# Power.net
KiCad netlist of a schematic drawn in Altium Designer
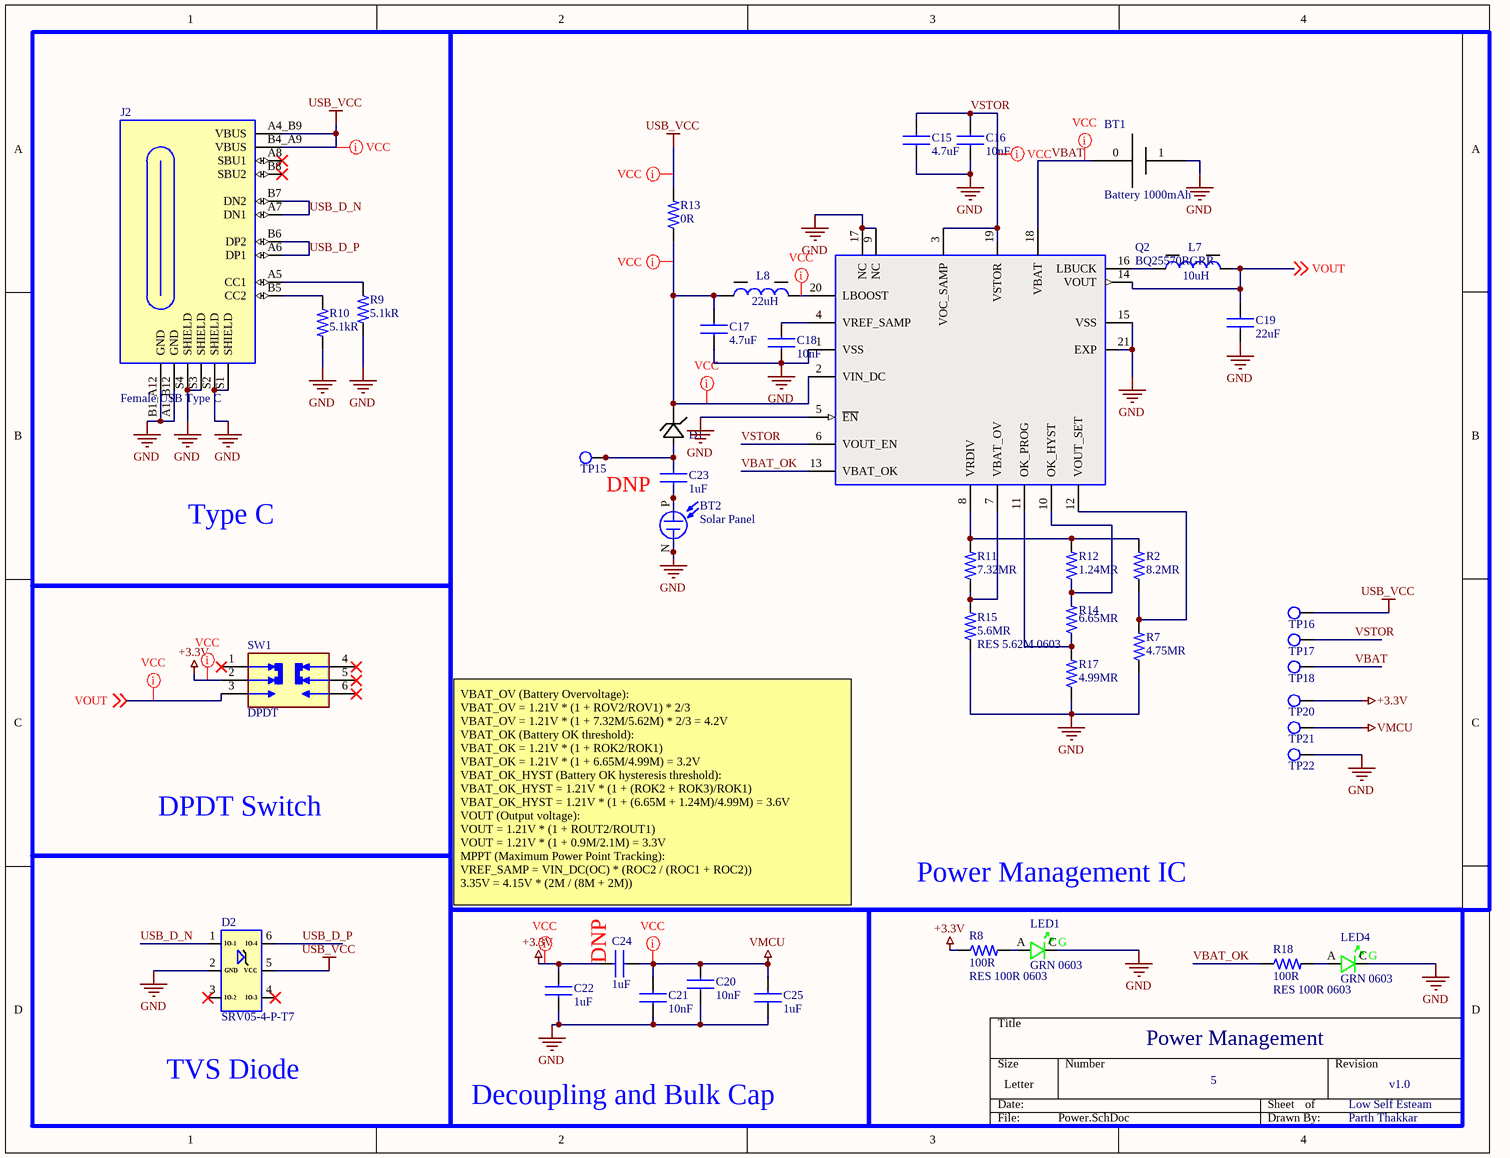
[diagram p0: Power.SchDoc]

(export (version "E")
  (design (tool "Eeschema 10.0.6"))
  (components
    (comp (ref "BT1")
      (value "Battery 1000mAh")
      (footprint "Battery")
      (description "Batt Lith-ion 3.7V 1.05AH 404852")
      (fields
        (field (name "MANUFACTURER") "GlobTek")
        (field (name "MANUFACTURER PART NUMBER") "BL1200P4054481S1PCAC")
      )
      (libsource (lib "Keyboard_parts") (part "Battery 1000mAh"))
    )
    (comp (ref "BT2")
      (value "Solar Panel")
      (footprint "Solar panel")
      (description "Monocryst Solar Cell 184MW 4.15V")
      (fields (field (name "MANUFACTURER") "ANYSOLAR") (field (name "MANUFACTURER PART NUMBER") "SM141K06L"))
      (libsource (lib "Keyboard_parts") (part "Solar Panel"))
    )
    (comp (ref "C15")
      (value "4.7uF")
      (footprint "Capacitor 0603")
      (fields
        (field (name "MANUFACTURER") "Murata")
        (field (name "MANUFACTURER PART NUMBER") "GRT188R61E475KE13D")
        (field (name "Comment") "CAP 4.7uF 25V 0603")
      )
      (libsource (lib "Keyboard_parts") (part "CAP 4.7uF 25V 0603"))
    )
    (comp (ref "C16")
      (value "10nF")
      (footprint "Capacitor 0603")
      (fields
        (field (name "MANUFACTURER") "Murata")
        (field (name "MANUFACTURER PART NUMBER") "GCM188R72A103KA37D")
        (field (name "Comment") "CAP 10nF 100V 0603")
      )
      (libsource (lib "Keyboard_parts") (part "CAP 10nF 100V 0603"))
    )
    (comp (ref "C17")
      (value "4.7uF")
      (footprint "Capacitor 0603")
      (fields
        (field (name "MANUFACTURER") "Murata")
        (field (name "MANUFACTURER PART NUMBER") "GRT188R61E475KE13D")
        (field (name "Comment") "CAP 4.7uF 25V 0603")
      )
      (libsource (lib "Keyboard_parts") (part "CAP 4.7uF 25V 0603"))
    )
    (comp (ref "C18")
      (value "10nF")
      (footprint "Capacitor 0603")
      (fields
        (field (name "MANUFACTURER") "Murata")
        (field (name "MANUFACTURER PART NUMBER") "GCM188R72A103KA37D")
        (field (name "Comment") "CAP 10nF 100V 0603")
      )
      (libsource (lib "Keyboard_parts") (part "CAP 10nF 100V 0603"))
    )
    (comp (ref "C19")
      (value "22uF")
      (footprint "Capacitor 0603")
      (fields
        (field (name "MANUFACTURER") "Murata")
        (field (name "MANUFACTURER PART NUMBER") "GRM188R61A226ME15D")
        (field (name "TOLERANCE") "20 %")
      )
      (libsource (lib "Keyboard_parts") (part "CAP 22uF 6.3V 0603"))
    )
    (comp (ref "C20")
      (value "10nF")
      (footprint "Capacitor 0603")
      (fields
        (field (name "MANUFACTURER") "Murata")
        (field (name "MANUFACTURER PART NUMBER") "GCM188R72A103KA37D")
        (field (name "Comment") "CAP 0.1uF 100V 0603")
      )
      (libsource (lib "Keyboard_parts") (part "CAP 0.1uF 100V 0603"))
    )
    (comp (ref "C21")
      (value "10nF")
      (footprint "Capacitor 0603")
      (fields
        (field (name "MANUFACTURER") "Murata")
        (field (name "MANUFACTURER PART NUMBER") "GCM188R72A103KA37D")
        (field (name "Comment") "CAP 0.1uF 100V 0603")
      )
      (libsource (lib "Keyboard_parts") (part "CAP 0.1uF 100V 0603"))
    )
    (comp (ref "C22")
      (value "1uF")
      (footprint "CAPACITOR 0805")
      (description "Multilayer Ceramic Capacitor, 1 uF, 10 V, ± 20%, X5R, 0201 [0603 Metric]")
      (fields
        (field (name "MANUFACTURER") "Murata")
        (field (name "MANUFACTURER PART NUMBER") "GRM033R61A105ME15D")
      )
      (libsource (lib "Keyboard_parts") (part "CAP 47uF 10V 0805"))
    )
    (comp (ref "C23")
      (value "1uF")
      (footprint "CAPACITOR 0805")
      (description "Multilayer Ceramic Capacitor, 1 uF, 10 V, ± 20%, X5R, 0201 [0603 Metric]")
      (fields
        (field (name "MANUFACTURER") "Murata")
        (field (name "MANUFACTURER PART NUMBER") "GRM033R61A105ME15D")
      )
      (libsource (lib "Keyboard_parts") (part "CAP 47uF 10V 0805"))
    )
    (comp (ref "C24")
      (value "1uF")
      (footprint "CAPACITOR 0805")
      (description "Multilayer Ceramic Capacitor, 1 uF, 10 V, ± 20%, X5R, 0201 [0603 Metric]")
      (fields
        (field (name "MANUFACTURER") "Murata")
        (field (name "MANUFACTURER PART NUMBER") "GRM033R61A105ME15D")
      )
      (libsource (lib "Keyboard_parts") (part "CAP 47uF 10V 0805"))
    )
    (comp (ref "C25")
      (value "1uF")
      (footprint "CAPACITOR 0805")
      (description "Multilayer Ceramic Capacitor, 1 uF, 10 V, ± 20%, X5R, 0201 [0603 Metric]")
      (fields
        (field (name "MANUFACTURER") "Murata")
        (field (name "MANUFACTURER PART NUMBER") "GRM033R61A105ME15D")
      )
      (libsource (lib "Keyboard_parts") (part "CAP 47uF 10V 0805"))
    )
    (comp (ref "D1")
      (value "Diode Schottky")
      (footprint "Diode Schottky")
      (description "Rectifier Diode, Schottky, 1 Phase, 1 Element, 1A, 15V V(RRM), Silicon, DO-214BA")
      (fields
        (field (name "MANUFACTURER") "Microchip")
        (field (name "MANUFACTURER PART NUMBER") "LSM115JE3/TR13")
      )
      (libsource (lib "Keyboard_parts") (part "Diode Schottky"))
    )
    (comp (ref "D2")
      (value "SRV05-4-P-T7")
      (footprint "TVS")
      (description "Trans Voltage Suppressor Diode, 300W, 5V V(RWM), Unidirectional, 1 Element, Silicon")
      (fields (field (name "LCSC PART#") "C85364") (field (name "MANUFACTURER") "Semtech"))
      (libsource (lib "Keyboard_parts") (part "D_TVS_Diode"))
    )
    (comp (ref "J2")
      (value "Female USB Type C")
      (footprint "Type C")
      (fields (field (name "MANUFACTURER PART NUMBER") "USB4125-GF-A_REVA2"))
      (libsource (lib "Keyboard_parts") (part "USB-C Power Connector"))
    )
    (comp (ref "L7")
      (value "IND 10uH 1111")
      (footprint "IND 10uH (1x3.2)")
      (description "General Purpose Inductor, 10uH, 30%, 1 Element, Ferrite-Core, SMD, 1111")
      (fields
        (field (name "MANUFACTURER") "Wurth Electronics")
        (field (name "MANUFACTURER PART NUMBER") "744029100")
        (field (name "INDUCTANCE-NOM (L)") "10uH")
      )
      (libsource (lib "Keyboard_parts") (part "IND 10uH 1111"))
    )
    (comp (ref "L8")
      (value "IND 22uH 1515")
      (footprint "IND 22uH (1.6x4.3)")
      (description "General Purpose Inductor, 22uH, 30%, 1 Element, Ferrite-Core, SMD, 1515")
      (fields
        (field (name "MANUFACTURER") "Wurth Electronics")
        (field (name "MANUFACTURER PART NUMBER") "744031220")
        (field (name "INDUCTANCE-NOM (L)") "22uH")
      )
      (libsource (lib "Keyboard_parts") (part "IND 22uH 1515"))
    )
    (comp (ref "LED1")
      (value "GRN 0603")
      (footprint "LED 0603")
      (description "LED, 0603, GREEN, 430MCD, 520NM")
      (fields
        (field (name "MANUFACTURER") "Wurth Electronics")
        (field (name "MANUFACTURER PART NUMBER") "150060GS75000")
      )
      (libsource (lib "Keyboard_parts") (part "LED Green 0603"))
    )
    (comp (ref "LED4")
      (value "GRN 0603")
      (footprint "LED 0603")
      (description "LED, 0603, GREEN, 430MCD, 520NM")
      (fields
        (field (name "MANUFACTURER") "Wurth Electronics")
        (field (name "MANUFACTURER PART NUMBER") "150060GS75000")
      )
      (libsource (lib "Keyboard_parts") (part "LED Green 0603"))
    )
    (comp (ref "Q2")
      (value "BQ25570RGRR")
      (footprint "BQ25570RGRR")
      (description "Power Supply Support Circuit, Adjustable, 1 Channel, PQCC20")
      (fields (field (name "MANUFACTURER") "Texas Instruments"))
      (libsource (lib "Keyboard_parts") (part "BQ25570RGRR"))
    )
    (comp (ref "R2")
      (value "8.2MR")
      (footprint "Resistor 0603")
      (fields
        (field (name "MANUFACTURER") "Yageo")
        (field (name "MANUFACTURER PART NUMBER") "RC0603JR-078M2L")
        (field (name "TOLERANCE") "5%")
      )
      (libsource (lib "Keyboard_parts") (part "RES 8.2M 0603"))
    )
    (comp (ref "R7")
      (value "4.75MR")
      (footprint "Resistor 0603")
      (fields
        (field (name "MANUFACTURER") "Yageo")
        (field (name "MANUFACTURER PART NUMBER") "RC0603FR-074M75L")
        (field (name "TOLERANCE") "1%")
      )
      (libsource (lib "Keyboard_parts") (part "RES 4.75M 0603"))
    )
    (comp (ref "R8")
      (value "RES 100R 0603")
      (footprint "Resistor 0603")
      (fields
        (field (name "MANUFACTURER") "Yageo")
        (field (name "MANUFACTURER PART NUMBER") "RC0603FR-07100RL")
        (field (name "TOLERANCE") "1%")
        (field (name "ALTIUM_VALUE") "100R")
      )
      (libsource (lib "Keyboard_parts") (part "RES 100R 0603"))
    )
    (comp (ref "R9")
      (value "5.1kR")
      (footprint "Resistor 0603")
      (fields
        (field (name "MANUFACTURER") "Yageo")
        (field (name "MANUFACTURER PART NUMBER") "RC0603FR-075K1L")
        (field (name "TOLERANCE") "1%")
      )
      (libsource (lib "Keyboard_parts") (part "RES 5.1K 0603"))
    )
    (comp (ref "R10")
      (value "5.1kR")
      (footprint "Resistor 0603")
      (fields
        (field (name "MANUFACTURER") "Yageo")
        (field (name "MANUFACTURER PART NUMBER") "RC0603FR-075K1L")
        (field (name "TOLERANCE") "1%")
      )
      (libsource (lib "Keyboard_parts") (part "RES 5.1K 0603"))
    )
    (comp (ref "R11")
      (value "7.32MR")
      (footprint "Resistor 0603")
      (fields
        (field (name "MANUFACTURER") "Yageo")
        (field (name "MANUFACTURER PART NUMBER") "RC0402FR-077M32L")
        (field (name "TOLERANCE") "1%")
      )
      (libsource (lib "Keyboard_parts") (part "RES 7.32M 0603"))
    )
    (comp (ref "R12")
      (value "1.24MR")
      (footprint "Resistor 0603")
      (fields
        (field (name "MANUFACTURER") "Yageo")
        (field (name "MANUFACTURER PART NUMBER") "RC0603FR-071M24L")
        (field (name "TOLERANCE") "1%")
      )
      (libsource (lib "Keyboard_parts") (part "RES 1.24M 0603"))
    )
    (comp (ref "R13")
      (value "0R")
      (footprint "Resistor 0402")
      (description "Metal Glaze/thick Film, 0.0625W, 0ohm, Surface Mount, 0402")
      (fields
        (field (name "MANUFACTURER") "Yageo")
        (field (name "MANUFACTURER PART NUMBER") "RC0402JR-070RL")
      )
      (libsource (lib "Keyboard_parts") (part "RES 0R 0402"))
    )
    (comp (ref "R14")
      (value "6.65MR")
      (footprint "Resistor 0603")
      (fields
        (field (name "MANUFACTURER") "Vishay")
        (field (name "MANUFACTURER PART NUMBER") "CRCW06036M65FKEA")
        (field (name "TOLERANCE") "1%")
      )
      (libsource (lib "Keyboard_parts") (part "RES 6.65M 0603"))
    )
    (comp (ref "R15")
      (value "RES 5.62M 0603")
      (footprint "Resistor 0603")
      (fields
        (field (name "MANUFACTURER") "Yageo")
        (field (name "MANUFACTURER PART NUMBER") "RC0603JR-075M6L")
        (field (name "TOLERANCE") "5%")
        (field (name "ALTIUM_VALUE") "5.6MR")
      )
      (libsource (lib "Keyboard_parts") (part "RES 5.62M 0603"))
    )
    (comp (ref "R17")
      (value "4.99MR")
      (footprint "Resistor 0603")
      (fields
        (field (name "MANUFACTURER") "Yageo")
        (field (name "MANUFACTURER PART NUMBER") "RC0603FR-074M99L")
        (field (name "TOLERANCE") "1%")
      )
      (libsource (lib "Keyboard_parts") (part "RES 4.99M 0603"))
    )
    (comp (ref "R18")
      (value "RES 100R 0603")
      (footprint "Resistor 0603")
      (fields
        (field (name "MANUFACTURER") "Yageo")
        (field (name "MANUFACTURER PART NUMBER") "RC0603FR-07100RL")
        (field (name "TOLERANCE") "1%")
        (field (name "ALTIUM_VALUE") "100R")
      )
      (libsource (lib "Keyboard_parts") (part "RES 100R 0603"))
    )
    (comp (ref "SW1")
      (value "DPDT")
      (footprint "DPDT")
      (description "Slide Switch, DPDT, Latched, Solder Terminal, Through Hole-right Angle")
      (fields (field (name "MANUFACTURER") "E-Switch") (field (name "MANUFACTURER PART NUMBER") "EG2208"))
      (libsource (lib "Keyboard_parts") (part "DPDT"))
    )
    (comp (ref "TP15")
      (value "Test point")
      (footprint "Test Point")
      (libsource (lib "Keyboard_parts") (part "Test point"))
    )
    (comp (ref "TP16")
      (value "Test point")
      (footprint "Test Point")
      (libsource (lib "Keyboard_parts") (part "Test point"))
    )
    (comp (ref "TP17")
      (value "Test point")
      (footprint "Test Point")
      (libsource (lib "Keyboard_parts") (part "Test point"))
    )
    (comp (ref "TP18")
      (value "Test point")
      (footprint "Test Point")
      (libsource (lib "Keyboard_parts") (part "Test point"))
    )
    (comp (ref "TP20")
      (value "Test point")
      (footprint "Test Point")
      (libsource (lib "Keyboard_parts") (part "Test point"))
    )
    (comp (ref "TP21")
      (value "Test point")
      (footprint "Test Point")
      (libsource (lib "Keyboard_parts") (part "Test point"))
    )
    (comp (ref "TP22")
      (value "Test point")
      (footprint "Test Point")
      (libsource (lib "Keyboard_parts") (part "Test point"))
    )
  )
  (nets
    (net (code "1") (name "+3.3V") (class "Default")
      (node (ref "C22") (pin "1") (pinfunction "1_1") (pintype "passive"))
      (node (ref "C24") (pin "1") (pinfunction "1_1") (pintype "passive"))
      (node (ref "R8") (pin "1") (pinfunction "1_1") (pintype "passive"))
      (node (ref "SW1") (pin "2") (pinfunction "2_2") (pintype "passive"))
      (node (ref "TP20") (pin "1") (pinfunction "1_1") (pintype "passive"))
    )
    (net (code "2") (name "/USB_D_N") (class "Default")
      (node (ref "D2") (pin "1") (pinfunction "IO-1_1") (pintype "passive"))
      (node (ref "J2") (pin "A7") (pinfunction "DN1_A7") (pintype "bidirectional"))
      (node (ref "J2") (pin "B7") (pinfunction "DN2_B7") (pintype "bidirectional"))
    )
    (net (code "3") (name "/USB_D_P") (class "Default")
      (node (ref "D2") (pin "6") (pinfunction "IO-4_6") (pintype "passive"))
      (node (ref "J2") (pin "A6") (pinfunction "DP1_A6") (pintype "bidirectional"))
      (node (ref "J2") (pin "B6") (pinfunction "DP2_B6") (pintype "bidirectional"))
    )
    (net (code "4") (name "/VBAT") (class "Default")
      (node (ref "BT1") (pin "0") (pinfunction "VCC_0") (pintype "passive"))
      (node (ref "Q2") (pin "18") (pinfunction "VBAT_18") (pintype "power_in"))
      (node (ref "TP18") (pin "1") (pinfunction "1_1") (pintype "passive"))
    )
    (net (code "5") (name "/VBAT_OK") (class "Default")
      (node (ref "Q2") (pin "13") (pinfunction "VBAT_OK_13") (pintype "passive"))
      (node (ref "R18") (pin "1") (pinfunction "1_1") (pintype "passive"))
    )
    (net (code "6") (name "/VSTOR") (class "Default")
      (node (ref "C15") (pin "1") (pinfunction "1_1") (pintype "passive"))
      (node (ref "C16") (pin "1") (pinfunction "1_1") (pintype "passive"))
      (node (ref "Q2") (pin "19") (pinfunction "VSTOR_19") (pintype "passive"))
      (node (ref "Q2") (pin "3") (pinfunction "VOC_SAMP_3") (pintype "passive"))
      (node (ref "Q2") (pin "6") (pinfunction "VOUT_EN_6") (pintype "passive"))
      (node (ref "TP17") (pin "1") (pinfunction "1_1") (pintype "passive"))
    )
    (net (code "7") (name "GND") (class "Default")
      (node (ref "BT1") (pin "1") (pinfunction "GND_1") (pintype "passive"))
      (node (ref "BT2") (pin "N") (pinfunction "N_N") (pintype "passive"))
      (node (ref "C15") (pin "2") (pinfunction "2_2") (pintype "passive"))
      (node (ref "C16") (pin "2") (pinfunction "2_2") (pintype "passive"))
      (node (ref "C17") (pin "2") (pinfunction "2_2") (pintype "passive"))
      (node (ref "C18") (pin "1") (pinfunction "1_1") (pintype "passive"))
      (node (ref "C19") (pin "2") (pinfunction "2_2") (pintype "passive"))
      (node (ref "C20") (pin "2") (pinfunction "2_2") (pintype "passive"))
      (node (ref "C21") (pin "2") (pinfunction "2_2") (pintype "passive"))
      (node (ref "C22") (pin "2") (pinfunction "2_2") (pintype "passive"))
      (node (ref "C25") (pin "2") (pinfunction "2_2") (pintype "passive"))
      (node (ref "D2") (pin "2") (pinfunction "GND_2") (pintype "passive"))
      (node (ref "J2") (pin "A1_B12") (pinfunction "GND_A1_B12") (pintype "power_in"))
      (node (ref "J2") (pin "B1_A12") (pinfunction "GND_B1_A12") (pintype "power_in"))
      (node (ref "J2") (pin "S1") (pinfunction "SHIELD_S1") (pintype "passive"))
      (node (ref "J2") (pin "S2") (pinfunction "SHIELD_S2") (pintype "passive"))
      (node (ref "J2") (pin "S3") (pinfunction "SHIELD_S3") (pintype "passive"))
      (node (ref "J2") (pin "S4") (pinfunction "SHIELD_S4") (pintype "passive"))
      (node (ref "LED1") (pin "C") (pinfunction "C_C") (pintype "passive"))
      (node (ref "LED4") (pin "C") (pinfunction "C_C") (pintype "passive"))
      (node (ref "Q2") (pin "1") (pinfunction "VSS_1") (pintype "passive"))
      (node (ref "Q2") (pin "15") (pinfunction "VSS_15") (pintype "passive"))
      (node (ref "Q2") (pin "17") (pinfunction "NC_17") (pintype "passive"))
      (node (ref "Q2") (pin "21") (pinfunction "EXP_21") (pintype "passive"))
      (node (ref "Q2") (pin "5") (pinfunction "~{EN}_5") (pintype "input"))
      (node (ref "Q2") (pin "9") (pinfunction "NC_9") (pintype "passive"))
      (node (ref "R10") (pin "2") (pinfunction "2_2") (pintype "passive"))
      (node (ref "R15") (pin "1") (pinfunction "1_1") (pintype "passive"))
      (node (ref "R17") (pin "1") (pinfunction "1_1") (pintype "passive"))
      (node (ref "R7") (pin "1") (pinfunction "1_1") (pintype "passive"))
      (node (ref "R9") (pin "2") (pinfunction "2_2") (pintype "passive"))
      (node (ref "TP22") (pin "1") (pinfunction "1_1") (pintype "passive"))
    )
    (net (code "8") (name "Net-(BT2-PadP)") (class "Default")
      (node (ref "BT2") (pin "P") (pinfunction "P_P") (pintype "passive"))
      (node (ref "C23") (pin "2") (pinfunction "2_2") (pintype "passive"))
    )
    (net (code "9") (name "Net-(C23-Pad1)") (class "Default")
      (node (ref "C23") (pin "1") (pinfunction "1_1") (pintype "passive"))
      (node (ref "D1") (pin "2") (pinfunction "2_2") (pintype "passive"))
      (node (ref "TP15") (pin "1") (pinfunction "1_1") (pintype "passive"))
    )
    (net (code "10") (name "Net-(J2-CC1)") (class "Default")
      (node (ref "J2") (pin "A5") (pinfunction "CC1_A5") (pintype "bidirectional"))
      (node (ref "R9") (pin "1") (pinfunction "1_1") (pintype "passive"))
    )
    (net (code "11") (name "Net-(J2-CC2)") (class "Default")
      (node (ref "J2") (pin "B5") (pinfunction "CC2_B5") (pintype "bidirectional"))
      (node (ref "R10") (pin "1") (pinfunction "1_1") (pintype "passive"))
    )
    (net (code "12") (name "Net-(LED1-PadA)") (class "Default")
      (node (ref "LED1") (pin "A") (pinfunction "A_A") (pintype "passive"))
      (node (ref "R8") (pin "2") (pinfunction "2_2") (pintype "passive"))
    )
    (net (code "13") (name "Net-(LED4-PadA)") (class "Default")
      (node (ref "LED4") (pin "A") (pinfunction "A_A") (pintype "passive"))
      (node (ref "R18") (pin "2") (pinfunction "2_2") (pintype "passive"))
    )
    (net (code "14") (name "Net-(Q2-LBOOST)") (class "Default")
      (node (ref "L8") (pin "2") (pinfunction "2_2") (pintype "passive"))
      (node (ref "Q2") (pin "20") (pinfunction "LBOOST_20") (pintype "power_in"))
    )
    (net (code "15") (name "Net-(Q2-LBUCK)") (class "Default")
      (node (ref "L7") (pin "1") (pinfunction "1_1") (pintype "passive"))
      (node (ref "Q2") (pin "16") (pinfunction "LBUCK_16") (pintype "power_in"))
    )
    (net (code "16") (name "Net-(Q2-OK_HYST)") (class "Default")
      (node (ref "Q2") (pin "10") (pinfunction "OK_HYST_10") (pintype "power_in"))
      (node (ref "R12") (pin "1") (pinfunction "1_1") (pintype "passive"))
      (node (ref "R14") (pin "2") (pinfunction "2_2") (pintype "passive"))
    )
    (net (code "17") (name "Net-(Q2-OK_PROG)") (class "Default")
      (node (ref "Q2") (pin "11") (pinfunction "OK_PROG_11") (pintype "power_in"))
      (node (ref "R14") (pin "1") (pinfunction "1_1") (pintype "passive"))
      (node (ref "R17") (pin "2") (pinfunction "2_2") (pintype "passive"))
    )
    (net (code "18") (name "Net-(Q2-VBAT_OV)") (class "Default")
      (node (ref "Q2") (pin "7") (pinfunction "VBAT_OV_7") (pintype "passive"))
      (node (ref "R11") (pin "1") (pinfunction "1_1") (pintype "passive"))
      (node (ref "R15") (pin "2") (pinfunction "2_2") (pintype "passive"))
    )
    (net (code "19") (name "Net-(Q2-VIN_DC)") (class "Default")
      (node (ref "C17") (pin "1") (pinfunction "1_1") (pintype "passive"))
      (node (ref "D1") (pin "1") (pinfunction "1_1") (pintype "passive"))
      (node (ref "L8") (pin "1") (pinfunction "1_1") (pintype "passive"))
      (node (ref "Q2") (pin "2") (pinfunction "VIN_DC_2") (pintype "passive"))
      (node (ref "R13") (pin "1") (pinfunction "1_1") (pintype "passive"))
    )
    (net (code "20") (name "Net-(Q2-VOUT_SET)") (class "Default")
      (node (ref "Q2") (pin "12") (pinfunction "VOUT_SET_12") (pintype "passive"))
      (node (ref "R2") (pin "1") (pinfunction "1_1") (pintype "passive"))
      (node (ref "R7") (pin "2") (pinfunction "2_2") (pintype "passive"))
    )
    (net (code "21") (name "Net-(Q2-VRDIV)") (class "Default")
      (node (ref "Q2") (pin "8") (pinfunction "VRDIV_8") (pintype "passive"))
      (node (ref "R11") (pin "2") (pinfunction "2_2") (pintype "passive"))
      (node (ref "R12") (pin "2") (pinfunction "2_2") (pintype "passive"))
      (node (ref "R2") (pin "2") (pinfunction "2_2") (pintype "passive"))
    )
    (net (code "22") (name "Net-(Q2-VREF_SAMP)") (class "Default")
      (node (ref "C18") (pin "2") (pinfunction "2_2") (pintype "passive"))
      (node (ref "Q2") (pin "4") (pinfunction "VREF_SAMP_4") (pintype "passive"))
    )
    (net (code "23") (name "USB_VCC") (class "Default")
      (node (ref "D2") (pin "5") (pinfunction "VCC_5") (pintype "passive"))
      (node (ref "J2") (pin "A4_B9") (pinfunction "VBUS_A4_B9") (pintype "power_in"))
      (node (ref "J2") (pin "B4_A9") (pinfunction "VBUS_B4_A9") (pintype "power_in"))
      (node (ref "R13") (pin "2") (pinfunction "2_2") (pintype "passive"))
      (node (ref "TP16") (pin "1") (pinfunction "1_1") (pintype "passive"))
    )
    (net (code "24") (name "VMCU") (class "Default")
      (node (ref "C20") (pin "1") (pinfunction "1_1") (pintype "passive"))
      (node (ref "C21") (pin "1") (pinfunction "1_1") (pintype "passive"))
      (node (ref "C24") (pin "2") (pinfunction "2_2") (pintype "passive"))
      (node (ref "C25") (pin "1") (pinfunction "1_1") (pintype "passive"))
      (node (ref "TP21") (pin "1") (pinfunction "1_1") (pintype "passive"))
    )
    (net (code "25") (name "VOUT") (class "Default")
      (node (ref "C19") (pin "1") (pinfunction "1_1") (pintype "passive"))
      (node (ref "L7") (pin "2") (pinfunction "2_2") (pintype "passive"))
      (node (ref "Q2") (pin "14") (pinfunction "VOUT_14") (pintype "output"))
      (node (ref "SW1") (pin "3") (pinfunction "3_3") (pintype "passive"))
    )
    (net (code "26") (name "unconnected-(D2-IO-2-Pad3)") (class "Default")
      (node (ref "D2") (pin "3") (pinfunction "IO-2_3") (pintype "passive+no_connect"))
    )
    (net (code "27") (name "unconnected-(D2-IO-3-Pad4)") (class "Default")
      (node (ref "D2") (pin "4") (pinfunction "IO-3_4") (pintype "passive+no_connect"))
    )
    (net (code "28") (name "unconnected-(J2-SBU1-PadA8)") (class "Default")
      (node (ref "J2") (pin "A8") (pinfunction "SBU1_A8") (pintype "bidirectional+no_connect"))
    )
    (net (code "29") (name "unconnected-(J2-SBU2-PadB8)") (class "Default")
      (node (ref "J2") (pin "B8") (pinfunction "SBU2_B8") (pintype "bidirectional+no_connect"))
    )
    (net (code "30") (name "unconnected-(SW1-Pad1)") (class "Default")
      (node (ref "SW1") (pin "1") (pinfunction "1_1") (pintype "passive+no_connect"))
    )
    (net (code "31") (name "unconnected-(SW1-Pad4)") (class "Default")
      (node (ref "SW1") (pin "4") (pinfunction "4_4") (pintype "passive+no_connect"))
    )
    (net (code "32") (name "unconnected-(SW1-Pad5)") (class "Default")
      (node (ref "SW1") (pin "5") (pinfunction "5_5") (pintype "passive+no_connect"))
    )
    (net (code "33") (name "unconnected-(SW1-Pad6)") (class "Default")
      (node (ref "SW1") (pin "6") (pinfunction "6_6") (pintype "passive+no_connect"))
    )
  )
)
